# gameboypocket.net
KiCad netlist of a schematic drawn in EAGLE
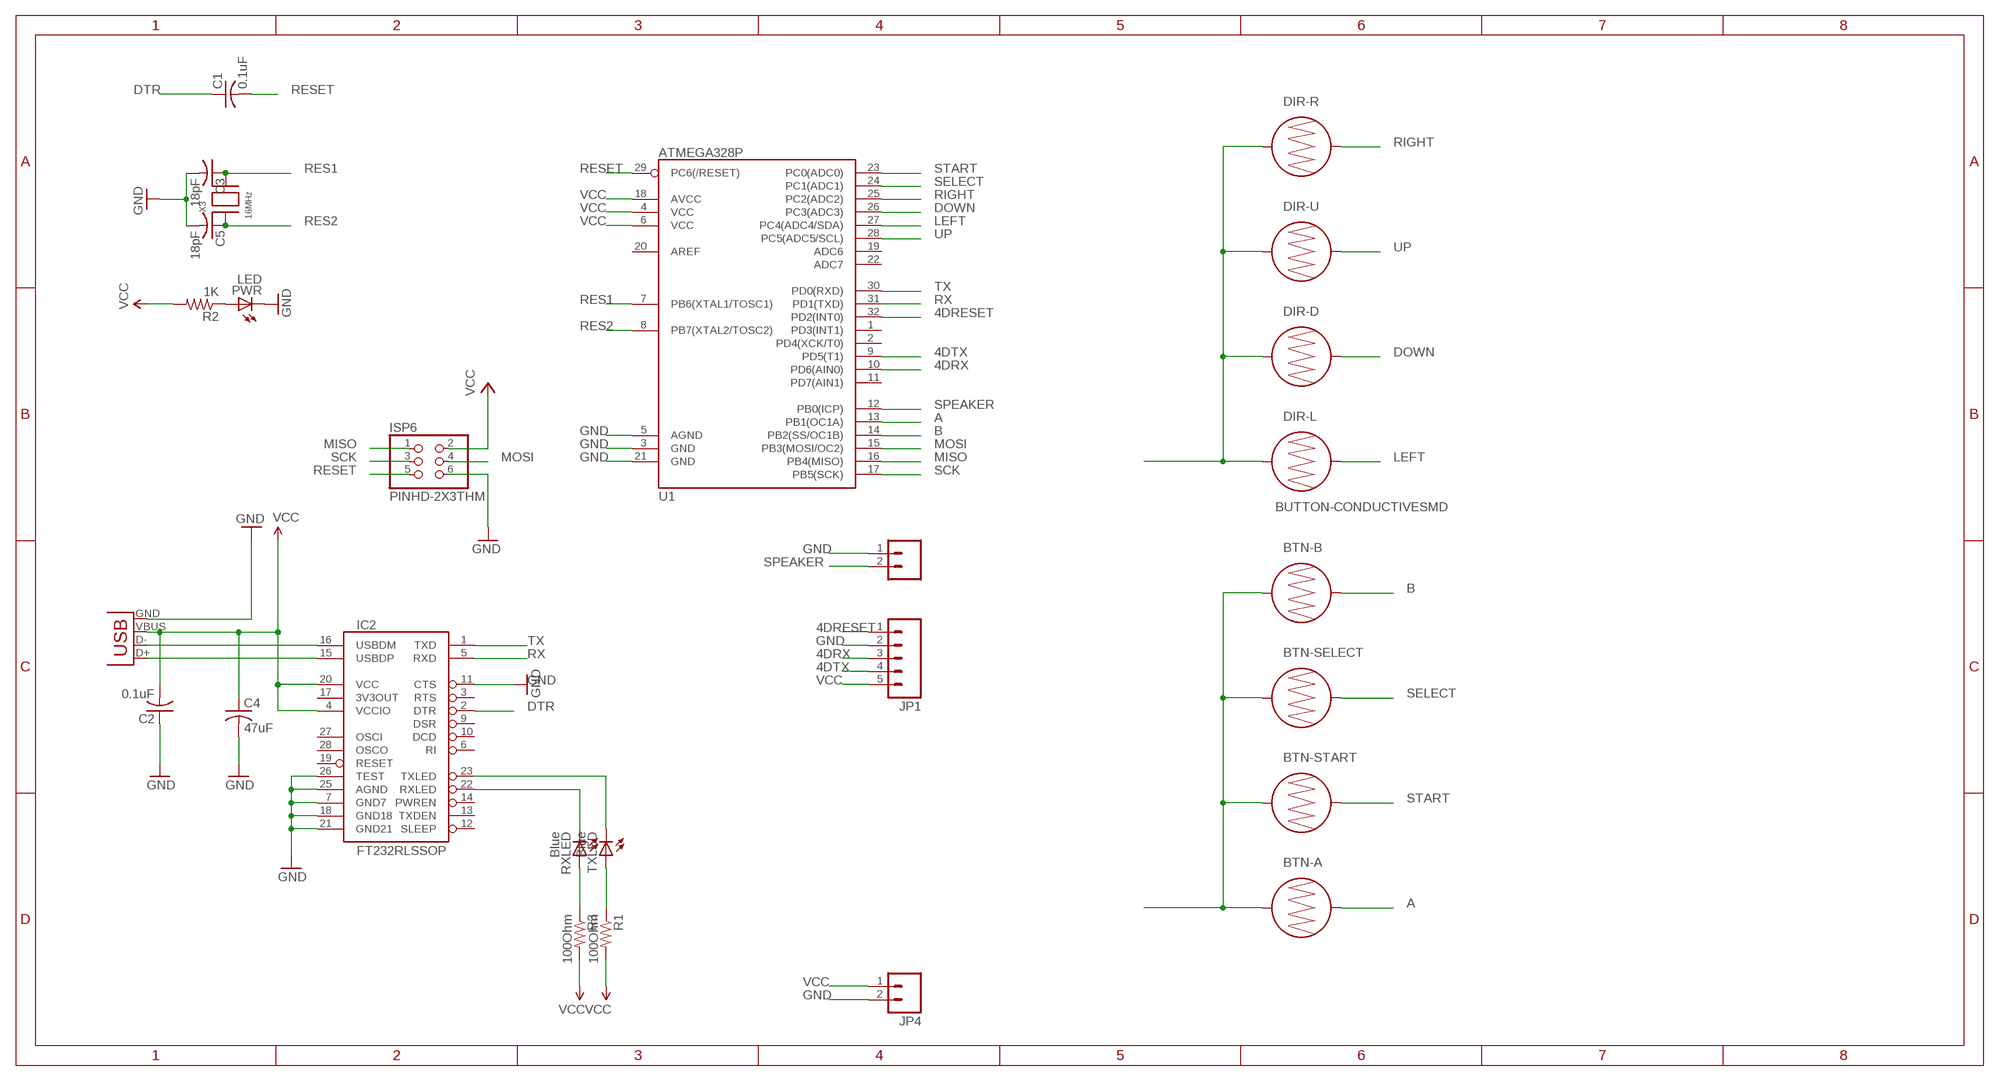
[diagram p0: schematic, sheet 1]

(export (version "E")
  (design (tool "Eeschema 10.0.6"))
  (components
    (comp (ref "BTN-A")
      (value "BUTTON-CONDUCTIVESMD")
      (footprint "eagle-import:BUTTON-CONDUCTIVE")
      (libsource (lib "eagle-import") (part "BUTTON-CONDUCTIVESMD"))
    )
    (comp (ref "BTN-B")
      (value "BUTTON-CONDUCTIVESMD")
      (footprint "eagle-import:BUTTON-CONDUCTIVE")
      (libsource (lib "eagle-import") (part "BUTTON-CONDUCTIVESMD"))
    )
    (comp (ref "BTN-SELECT")
      (value "BUTTON-CONDUCTIVESMD")
      (footprint "eagle-import:BUTTON-CONDUCTIVE")
      (libsource (lib "eagle-import") (part "BUTTON-CONDUCTIVESMD"))
    )
    (comp (ref "BTN-START")
      (value "BUTTON-CONDUCTIVESMD")
      (footprint "eagle-import:BUTTON-CONDUCTIVE")
      (libsource (lib "eagle-import") (part "BUTTON-CONDUCTIVESMD"))
    )
    (comp (ref "C1")
      (value "0.1uF")
      (footprint "eagle-import:C0805K")
      (libsource (lib "eagle-import") (part "rcl_C-USC0805K"))
    )
    (comp (ref "C2")
      (value "0.1uF")
      (footprint "eagle-import:C0805K")
      (libsource (lib "eagle-import") (part "rcl_C-USC0805K"))
    )
    (comp (ref "C3")
      (value "18pF")
      (footprint "eagle-import:C0805K")
      (libsource (lib "eagle-import") (part "C-USC0805K"))
    )
    (comp (ref "C4")
      (value "47uF")
      (footprint "eagle-import:C1206")
      (libsource (lib "eagle-import") (part "rcl_C-USC1206"))
    )
    (comp (ref "C5")
      (value "18pF")
      (footprint "eagle-import:C0805K")
      (libsource (lib "eagle-import") (part "C-USC0805K"))
    )
    (comp (ref "DIR-D")
      (value "BUTTON-CONDUCTIVESMD")
      (footprint "eagle-import:BUTTON-CONDUCTIVE")
      (libsource (lib "eagle-import") (part "BUTTON-CONDUCTIVESMD"))
    )
    (comp (ref "DIR-L")
      (value "BUTTON-CONDUCTIVESMD")
      (footprint "eagle-import:BUTTON-CONDUCTIVE")
      (libsource (lib "eagle-import") (part "BUTTON-CONDUCTIVESMD"))
    )
    (comp (ref "DIR-R")
      (value "BUTTON-CONDUCTIVESMD")
      (footprint "eagle-import:BUTTON-CONDUCTIVE")
      (libsource (lib "eagle-import") (part "BUTTON-CONDUCTIVESMD"))
    )
    (comp (ref "DIR-U")
      (value "BUTTON-CONDUCTIVESMD")
      (footprint "eagle-import:BUTTON-CONDUCTIVE")
      (libsource (lib "eagle-import") (part "BUTTON-CONDUCTIVESMD"))
    )
    (comp (ref "IC2")
      (value "FT232RLSSOP")
      (footprint "eagle-import:SSOP28DB")
      (libsource (lib "eagle-import") (part "FT232RLSSOP"))
    )
    (comp (ref "ISP6")
      (value "PINHD-2X3THM")
      (footprint "eagle-import:ISP6")
      (libsource (lib "eagle-import") (part "PINHD-2X3THM"))
    )
    (comp (ref "JP1")
      (value "M05PTH")
      (footprint "eagle-import:1X05")
      (libsource (lib "eagle-import") (part "M05PTH"))
    )
    (comp (ref "JP2")
      (value "M02PTH")
      (footprint "eagle-import:1X02")
      (libsource (lib "eagle-import") (part "M02PTH"))
    )
    (comp (ref "JP4")
      (value "M02JST-PTH-2")
      (footprint "eagle-import:JST-2-PTH")
      (libsource (lib "eagle-import") (part "M02JST-PTH-2"))
    )
    (comp (ref "PWR")
      (value "LED")
      (footprint "eagle-import:CHIPLED_0805")
      (libsource (lib "eagle-import") (part "LEDCHIPLED_0805"))
    )
    (comp (ref "R1")
      (value "100Ohm")
      (footprint "eagle-import:R0805")
      (libsource (lib "eagle-import") (part "R-US_R0805"))
    )
    (comp (ref "R2")
      (value "1K")
      (footprint "eagle-import:R0805")
      (libsource (lib "eagle-import") (part "R-US_R0805"))
    )
    (comp (ref "R3")
      (value "100Ohm")
      (footprint "eagle-import:R0805")
      (libsource (lib "eagle-import") (part "R-US_R0805"))
    )
    (comp (ref "RXLED")
      (value "Blue")
      (footprint "eagle-import:CHIPLED_0805")
      (libsource (lib "eagle-import") (part "led_LEDCHIPLED_0805"))
    )
    (comp (ref "TXLED")
      (value "Blue")
      (footprint "eagle-import:CHIPLED_0805")
      (libsource (lib "eagle-import") (part "led_LEDCHIPLED_0805"))
    )
    (comp (ref "U1")
      (value "ATMEGA328P")
      (footprint "eagle-import:TQFP32-08")
      (libsource (lib "eagle-import") (part "ATMEGA168"))
    )
    (comp (ref "X1")
      (value "USBSMD")
      (footprint "eagle-import:USB-MINIB")
      (libsource (lib "eagle-import") (part "USBSMD"))
    )
    (comp (ref "X3")
      (value "16MHz")
      (footprint "eagle-import:NX5032")
      (libsource (lib "eagle-import") (part "XTALNX5032"))
    )
  )
  (nets
    (net (code "1") (name "/4DRESET") (class "Default")
      (node (ref "JP1") (pin "1") (pinfunction "1_1") (pintype "passive"))
      (node (ref "U1") (pin "32") (pinfunction "PD2(INT0)_32") (pintype "bidirectional"))
    )
    (net (code "2") (name "/4DRX") (class "Default")
      (node (ref "JP1") (pin "3") (pinfunction "3_3") (pintype "passive"))
      (node (ref "U1") (pin "10") (pinfunction "PD6(AIN0)_10") (pintype "bidirectional"))
    )
    (net (code "3") (name "/4DTX") (class "Default")
      (node (ref "JP1") (pin "4") (pinfunction "4_4") (pintype "passive"))
      (node (ref "U1") (pin "9") (pinfunction "PD5(T1)_9") (pintype "bidirectional"))
    )
    (net (code "4") (name "/A") (class "Default")
      (node (ref "BTN-A") (pin "2") (pinfunction "2_2") (pintype "passive"))
      (node (ref "U1") (pin "13") (pinfunction "PB1(OC1A)_13") (pintype "bidirectional"))
    )
    (net (code "5") (name "/B") (class "Default")
      (node (ref "BTN-B") (pin "2") (pinfunction "2_2") (pintype "passive"))
      (node (ref "U1") (pin "14") (pinfunction "PB2(SS/OC1B)_14") (pintype "bidirectional"))
    )
    (net (code "6") (name "/DOWN") (class "Default")
      (node (ref "DIR-D") (pin "2") (pinfunction "2_2") (pintype "passive"))
      (node (ref "U1") (pin "26") (pinfunction "PC3(ADC3)_26") (pintype "bidirectional"))
    )
    (net (code "7") (name "/DTR") (class "Default")
      (node (ref "C1") (pin "1") (pinfunction "1_1") (pintype "passive"))
      (node (ref "IC2") (pin "2") (pinfunction "DTR_2") (pintype "output"))
    )
    (net (code "8") (name "/LEFT") (class "Default")
      (node (ref "DIR-L") (pin "2") (pinfunction "2_2") (pintype "passive"))
      (node (ref "U1") (pin "27") (pinfunction "PC4(ADC4/SDA)_27") (pintype "bidirectional"))
    )
    (net (code "9") (name "/MISO") (class "Default")
      (node (ref "ISP6") (pin "1") (pinfunction "1_1") (pintype "passive"))
      (node (ref "U1") (pin "16") (pinfunction "PB4(MISO)_16") (pintype "bidirectional"))
    )
    (net (code "10") (name "/MOSI") (class "Default")
      (node (ref "ISP6") (pin "4") (pinfunction "4_4") (pintype "passive"))
      (node (ref "U1") (pin "15") (pinfunction "PB3(MOSI/OC2)_15") (pintype "bidirectional"))
    )
    (net (code "11") (name "/RES1") (class "Default")
      (node (ref "C3") (pin "1") (pinfunction "1_1") (pintype "passive"))
      (node (ref "U1") (pin "7") (pinfunction "PB6(XTAL1/TOSC1)_7") (pintype "bidirectional"))
      (node (ref "X3") (pin "P$2") (pinfunction "P$2_P$2") (pintype "bidirectional"))
    )
    (net (code "12") (name "/RES2") (class "Default")
      (node (ref "C5") (pin "1") (pinfunction "1_1") (pintype "passive"))
      (node (ref "U1") (pin "8") (pinfunction "PB7(XTAL2/TOSC2)_8") (pintype "bidirectional"))
      (node (ref "X3") (pin "P$1") (pinfunction "P$1_P$1") (pintype "bidirectional"))
    )
    (net (code "13") (name "/RESET") (class "Default")
      (node (ref "C1") (pin "2") (pinfunction "2_2") (pintype "passive"))
      (node (ref "ISP6") (pin "5") (pinfunction "5_5") (pintype "passive"))
      (node (ref "U1") (pin "29") (pinfunction "PC6(/RESET)_29") (pintype "bidirectional"))
    )
    (net (code "14") (name "/RIGHT") (class "Default")
      (node (ref "DIR-R") (pin "2") (pinfunction "2_2") (pintype "passive"))
      (node (ref "U1") (pin "25") (pinfunction "PC2(ADC2)_25") (pintype "bidirectional"))
    )
    (net (code "15") (name "/RX") (class "Default")
      (node (ref "IC2") (pin "5") (pinfunction "RXD_5") (pintype "input"))
      (node (ref "U1") (pin "31") (pinfunction "PD1(TXD)_31") (pintype "bidirectional"))
    )
    (net (code "16") (name "/SCK") (class "Default")
      (node (ref "ISP6") (pin "3") (pinfunction "3_3") (pintype "passive"))
      (node (ref "U1") (pin "17") (pinfunction "PB5(SCK)_17") (pintype "bidirectional"))
    )
    (net (code "17") (name "/SELECT") (class "Default")
      (node (ref "BTN-SELECT") (pin "2") (pinfunction "2_2") (pintype "passive"))
      (node (ref "U1") (pin "24") (pinfunction "PC1(ADC1)_24") (pintype "bidirectional"))
    )
    (net (code "18") (name "/SPEAKER") (class "Default")
      (node (ref "JP2") (pin "2") (pinfunction "2_2") (pintype "passive"))
      (node (ref "U1") (pin "12") (pinfunction "PB0(ICP)_12") (pintype "bidirectional"))
    )
    (net (code "19") (name "/START") (class "Default")
      (node (ref "BTN-START") (pin "2") (pinfunction "2_2") (pintype "passive"))
      (node (ref "U1") (pin "23") (pinfunction "PC0(ADC0)_23") (pintype "bidirectional"))
    )
    (net (code "20") (name "/TX") (class "Default")
      (node (ref "IC2") (pin "1") (pinfunction "TXD_1") (pintype "output"))
      (node (ref "U1") (pin "30") (pinfunction "PD0(RXD)_30") (pintype "bidirectional"))
    )
    (net (code "21") (name "/UP") (class "Default")
      (node (ref "DIR-U") (pin "2") (pinfunction "2_2") (pintype "passive"))
      (node (ref "U1") (pin "28") (pinfunction "PC5(ADC5/SCL)_28") (pintype "bidirectional"))
    )
    (net (code "22") (name "GND") (class "Default")
      (node (ref "BTN-A") (pin "1") (pinfunction "1_1") (pintype "passive"))
      (node (ref "BTN-B") (pin "1") (pinfunction "1_1") (pintype "passive"))
      (node (ref "BTN-SELECT") (pin "1") (pinfunction "1_1") (pintype "passive"))
      (node (ref "BTN-START") (pin "1") (pinfunction "1_1") (pintype "passive"))
      (node (ref "C2") (pin "1") (pinfunction "1_1") (pintype "passive"))
      (node (ref "C3") (pin "2") (pinfunction "2_2") (pintype "passive"))
      (node (ref "C4") (pin "2") (pinfunction "2_2") (pintype "passive"))
      (node (ref "C5") (pin "2") (pinfunction "2_2") (pintype "passive"))
      (node (ref "DIR-D") (pin "1") (pinfunction "1_1") (pintype "passive"))
      (node (ref "DIR-L") (pin "1") (pinfunction "1_1") (pintype "passive"))
      (node (ref "DIR-R") (pin "1") (pinfunction "1_1") (pintype "passive"))
      (node (ref "DIR-U") (pin "1") (pinfunction "1_1") (pintype "passive"))
      (node (ref "IC2") (pin "11") (pinfunction "CTS_11") (pintype "input"))
      (node (ref "IC2") (pin "18") (pinfunction "GND18_18") (pintype "power_in"))
      (node (ref "IC2") (pin "21") (pinfunction "GND21_21") (pintype "power_in"))
      (node (ref "IC2") (pin "25") (pinfunction "AGND_25") (pintype "power_in"))
      (node (ref "IC2") (pin "26") (pinfunction "TEST_26") (pintype "input"))
      (node (ref "IC2") (pin "7") (pinfunction "GND7_7") (pintype "power_in"))
      (node (ref "ISP6") (pin "6") (pinfunction "6_6") (pintype "passive"))
      (node (ref "JP1") (pin "2") (pinfunction "2_2") (pintype "passive"))
      (node (ref "JP2") (pin "1") (pinfunction "1_1") (pintype "passive"))
      (node (ref "JP4") (pin "2") (pinfunction "2_2") (pintype "passive"))
      (node (ref "PWR") (pin "C") (pinfunction "C_C") (pintype "passive"))
      (node (ref "U1") (pin "21") (pinfunction "GND_21") (pintype "bidirectional"))
      (node (ref "U1") (pin "3") (pinfunction "GND_3") (pintype "bidirectional"))
      (node (ref "U1") (pin "5") (pinfunction "AGND_5") (pintype "bidirectional"))
      (node (ref "X1") (pin "GND") (pinfunction "GND_GND") (pintype "bidirectional"))
    )
    (net (code "23") (name "Net-(IC2-RXLED)") (class "Default")
      (node (ref "IC2") (pin "22") (pinfunction "RXLED_22") (pintype "input"))
      (node (ref "RXLED") (pin "C") (pinfunction "C_C") (pintype "passive"))
    )
    (net (code "24") (name "Net-(IC2-TXLED)") (class "Default")
      (node (ref "IC2") (pin "23") (pinfunction "TXLED_23") (pintype "input"))
      (node (ref "TXLED") (pin "C") (pinfunction "C_C") (pintype "passive"))
    )
    (net (code "25") (name "Net-(IC2-USBDM)") (class "Default")
      (node (ref "IC2") (pin "16") (pinfunction "USBDM_16") (pintype "bidirectional"))
      (node (ref "X1") (pin "D-") (pinfunction "D-_D-") (pintype "bidirectional"))
    )
    (net (code "26") (name "Net-(IC2-USBDP)") (class "Default")
      (node (ref "IC2") (pin "15") (pinfunction "USBDP_15") (pintype "bidirectional"))
      (node (ref "X1") (pin "D+") (pinfunction "D+_D+") (pintype "bidirectional"))
    )
    (net (code "27") (name "Net-(PWR-PadA)") (class "Default")
      (node (ref "PWR") (pin "A") (pinfunction "A_A") (pintype "passive"))
      (node (ref "R2") (pin "1") (pinfunction "1_1") (pintype "passive"))
    )
    (net (code "28") (name "Net-(R1-Pad1)") (class "Default")
      (node (ref "R1") (pin "1") (pinfunction "1_1") (pintype "passive"))
      (node (ref "TXLED") (pin "A") (pinfunction "A_A") (pintype "passive"))
    )
    (net (code "29") (name "Net-(R3-Pad1)") (class "Default")
      (node (ref "R3") (pin "1") (pinfunction "1_1") (pintype "passive"))
      (node (ref "RXLED") (pin "A") (pinfunction "A_A") (pintype "passive"))
    )
    (net (code "30") (name "VCC") (class "Default")
      (node (ref "C2") (pin "2") (pinfunction "2_2") (pintype "passive"))
      (node (ref "C4") (pin "1") (pinfunction "1_1") (pintype "passive"))
      (node (ref "IC2") (pin "20") (pinfunction "VCC_20") (pintype "power_in"))
      (node (ref "IC2") (pin "4") (pinfunction "VCCIO_4") (pintype "power_in"))
      (node (ref "ISP6") (pin "2") (pinfunction "2_2") (pintype "passive"))
      (node (ref "JP1") (pin "5") (pinfunction "5_5") (pintype "passive"))
      (node (ref "JP4") (pin "1") (pinfunction "1_1") (pintype "passive"))
      (node (ref "R1") (pin "2") (pinfunction "2_2") (pintype "passive"))
      (node (ref "R2") (pin "2") (pinfunction "2_2") (pintype "passive"))
      (node (ref "R3") (pin "2") (pinfunction "2_2") (pintype "passive"))
      (node (ref "U1") (pin "18") (pinfunction "AVCC_18") (pintype "bidirectional"))
      (node (ref "U1") (pin "4") (pinfunction "VCC_4") (pintype "bidirectional"))
      (node (ref "U1") (pin "6") (pinfunction "VCC_6") (pintype "bidirectional"))
      (node (ref "X1") (pin "VBUS") (pinfunction "VBUS_VBUS") (pintype "bidirectional"))
    )
    (net (code "31") (name "unconnected-(IC2-3V3OUT-Pad17)") (class "Default")
      (node (ref "IC2") (pin "17") (pinfunction "3V3OUT_17") (pintype "output"))
    )
    (net (code "32") (name "unconnected-(IC2-DCD-Pad10)") (class "Default")
      (node (ref "IC2") (pin "10") (pinfunction "DCD_10") (pintype "input"))
    )
    (net (code "33") (name "unconnected-(IC2-DSR-Pad9)") (class "Default")
      (node (ref "IC2") (pin "9") (pinfunction "DSR_9") (pintype "input"))
    )
    (net (code "34") (name "unconnected-(IC2-OSCI-Pad27)") (class "Default")
      (node (ref "IC2") (pin "27") (pinfunction "OSCI_27") (pintype "input"))
    )
    (net (code "35") (name "unconnected-(IC2-OSCO-Pad28)") (class "Default")
      (node (ref "IC2") (pin "28") (pinfunction "OSCO_28") (pintype "output"))
    )
    (net (code "36") (name "unconnected-(IC2-PWREN-Pad14)") (class "Default")
      (node (ref "IC2") (pin "14") (pinfunction "PWREN_14") (pintype "input"))
    )
    (net (code "37") (name "unconnected-(IC2-RESET-Pad19)") (class "Default")
      (node (ref "IC2") (pin "19") (pinfunction "RESET_19") (pintype "input"))
    )
    (net (code "38") (name "unconnected-(IC2-RI-Pad6)") (class "Default")
      (node (ref "IC2") (pin "6") (pinfunction "RI_6") (pintype "input"))
    )
    (net (code "39") (name "unconnected-(IC2-RTS-Pad3)") (class "Default")
      (node (ref "IC2") (pin "3") (pinfunction "RTS_3") (pintype "output"))
    )
    (net (code "40") (name "unconnected-(IC2-SLEEP-Pad12)") (class "Default")
      (node (ref "IC2") (pin "12") (pinfunction "SLEEP_12") (pintype "input"))
    )
    (net (code "41") (name "unconnected-(IC2-TXDEN-Pad13)") (class "Default")
      (node (ref "IC2") (pin "13") (pinfunction "TXDEN_13") (pintype "input"))
    )
    (net (code "42") (name "unconnected-(U1-ADC6-Pad19)") (class "Default")
      (node (ref "U1") (pin "19") (pinfunction "ADC6_19") (pintype "bidirectional"))
    )
    (net (code "43") (name "unconnected-(U1-ADC7-Pad22)") (class "Default")
      (node (ref "U1") (pin "22") (pinfunction "ADC7_22") (pintype "bidirectional"))
    )
    (net (code "44") (name "unconnected-(U1-AREF-Pad20)") (class "Default")
      (node (ref "U1") (pin "20") (pinfunction "AREF_20") (pintype "bidirectional"))
    )
    (net (code "45") (name "unconnected-(U1-PD3(INT1)-Pad1)") (class "Default")
      (node (ref "U1") (pin "1") (pinfunction "PD3(INT1)_1") (pintype "bidirectional"))
    )
    (net (code "46") (name "unconnected-(U1-PD4(XCK{slash}T0)-Pad2)") (class "Default")
      (node (ref "U1") (pin "2") (pinfunction "PD4(XCK/T0)_2") (pintype "bidirectional"))
    )
    (net (code "47") (name "unconnected-(U1-PD7(AIN1)-Pad11)") (class "Default")
      (node (ref "U1") (pin "11") (pinfunction "PD7(AIN1)_11") (pintype "bidirectional"))
    )
  )
)
